# sch_Power.net
KiCad netlist of a schematic drawn in Altium Designer
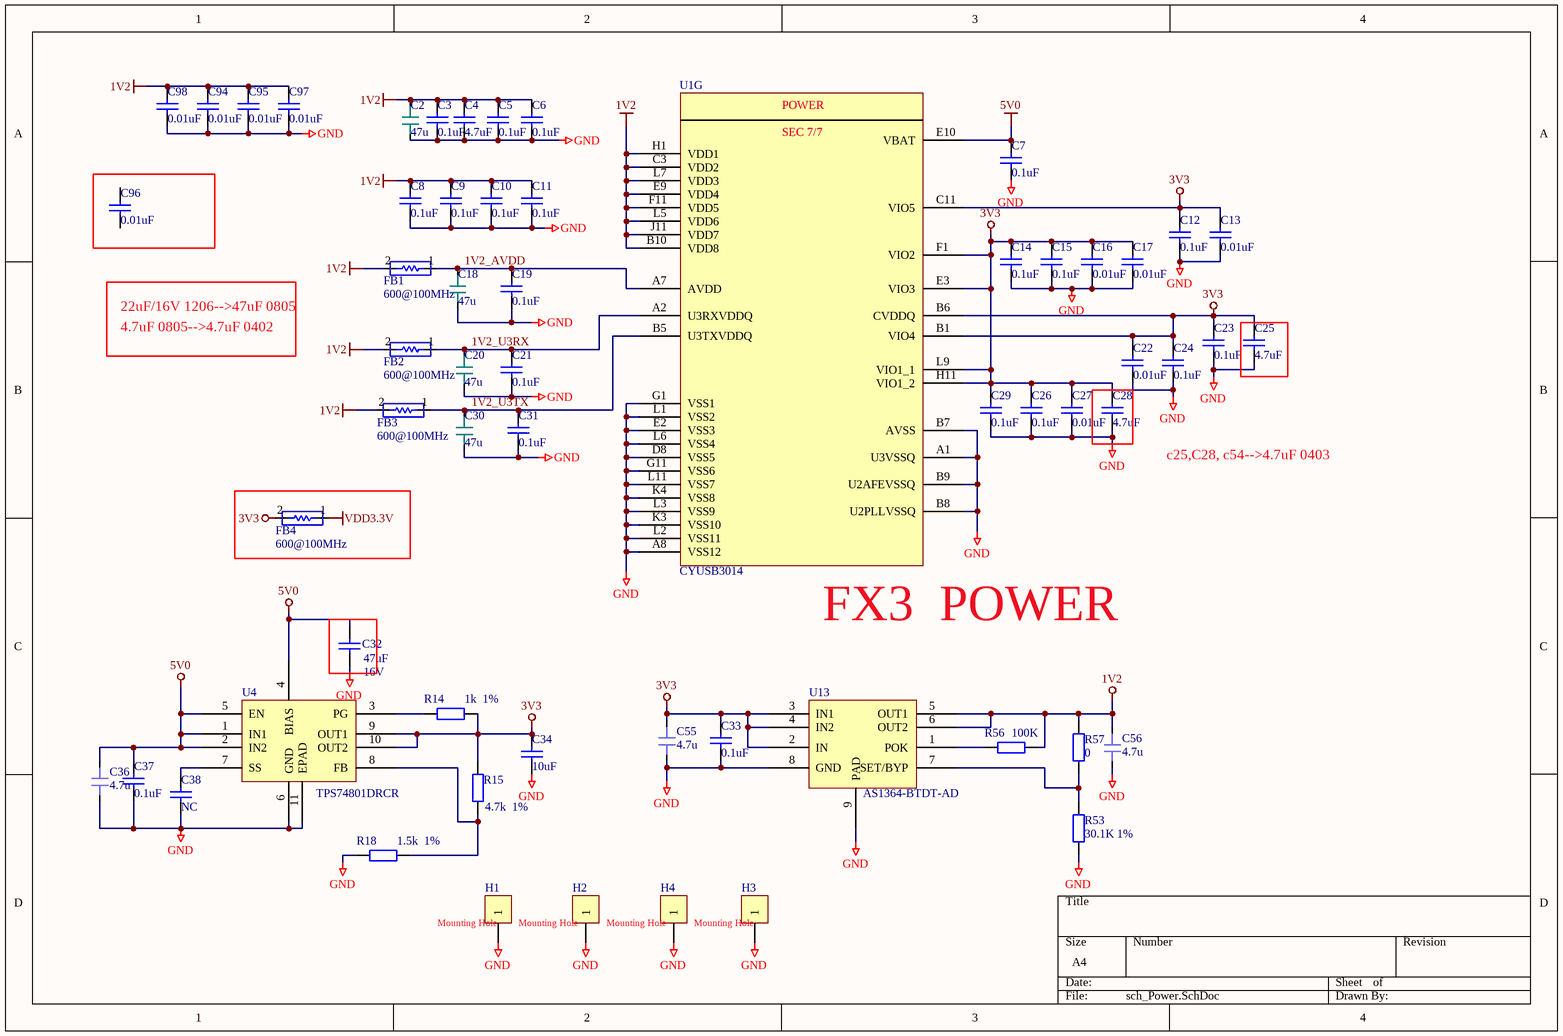
[diagram p0: sch_Power.SchDoc]

(export (version "E")
  (design (tool "Eeschema 10.0.6"))
  (components
    (comp (ref "C2")
      (value "47u")
      (footprint "0805C")
      (description "CC08052B476M5B20D")
      (libsource (lib "V0P1") (part "cap0805"))
    )
    (comp (ref "C3")
      (value "0.1uF")
      (footprint "0402C")
      (description "Capacitor")
      (fields (field (name "PUBLISHER") "Altium Limited"))
      (libsource (lib "Miscellaneous Devices") (part "Cap"))
    )
    (comp (ref "C4")
      (value "4.7uF")
      (footprint "0402C")
      (description "Capacitor")
      (fields (field (name "Comment") "0.1uF") (field (name "PUBLISHER") "Altium Limited"))
      (libsource (lib "Miscellaneous Devices") (part "Cap"))
    )
    (comp (ref "C5")
      (value "0.1uF")
      (footprint "0402C")
      (description "Capacitor")
      (fields (field (name "PUBLISHER") "Altium Limited"))
      (libsource (lib "Miscellaneous Devices") (part "Cap"))
    )
    (comp (ref "C6")
      (value "0.1uF")
      (footprint "0402C")
      (description "Capacitor")
      (fields (field (name "PUBLISHER") "Altium Limited"))
      (libsource (lib "Miscellaneous Devices") (part "Cap"))
    )
    (comp (ref "C7")
      (value "0.1uF")
      (footprint "0402C")
      (description "Capacitor")
      (fields (field (name "PUBLISHER") "Altium Limited"))
      (libsource (lib "Miscellaneous Devices") (part "Cap"))
    )
    (comp (ref "C8")
      (value "0.1uF")
      (footprint "0402C")
      (description "Capacitor")
      (fields (field (name "PUBLISHER") "Altium Limited"))
      (libsource (lib "Miscellaneous Devices") (part "Cap"))
    )
    (comp (ref "C9")
      (value "0.1uF")
      (footprint "0402C")
      (description "Capacitor")
      (fields (field (name "PUBLISHER") "Altium Limited"))
      (libsource (lib "Miscellaneous Devices") (part "Cap"))
    )
    (comp (ref "C10")
      (value "0.1uF")
      (footprint "0402C")
      (description "Capacitor")
      (fields (field (name "PUBLISHER") "Altium Limited"))
      (libsource (lib "Miscellaneous Devices") (part "Cap"))
    )
    (comp (ref "C11")
      (value "0.1uF")
      (footprint "0402C")
      (description "Capacitor")
      (fields (field (name "PUBLISHER") "Altium Limited"))
      (libsource (lib "Miscellaneous Devices") (part "Cap"))
    )
    (comp (ref "C12")
      (value "0.1uF")
      (footprint "0402C")
      (description "Capacitor")
      (fields (field (name "PUBLISHER") "Altium Limited"))
      (libsource (lib "Miscellaneous Devices") (part "Cap"))
    )
    (comp (ref "C13")
      (value "0.01uF")
      (footprint "0402C")
      (description "Capacitor")
      (fields (field (name "PUBLISHER") "Altium Limited"))
      (libsource (lib "Miscellaneous Devices") (part "Cap"))
    )
    (comp (ref "C14")
      (value "0.1uF")
      (footprint "0402C")
      (description "Capacitor")
      (fields (field (name "PUBLISHER") "Altium Limited"))
      (libsource (lib "Miscellaneous Devices") (part "Cap"))
    )
    (comp (ref "C15")
      (value "0.1uF")
      (footprint "0402C")
      (description "Capacitor")
      (fields (field (name "PUBLISHER") "Altium Limited"))
      (libsource (lib "Miscellaneous Devices") (part "Cap"))
    )
    (comp (ref "C16")
      (value "0.01uF")
      (footprint "0402C")
      (description "Capacitor")
      (fields (field (name "PUBLISHER") "Altium Limited"))
      (libsource (lib "Miscellaneous Devices") (part "Cap"))
    )
    (comp (ref "C17")
      (value "0.01uF")
      (footprint "0402C")
      (description "Capacitor")
      (fields (field (name "PUBLISHER") "Altium Limited"))
      (libsource (lib "Miscellaneous Devices") (part "Cap"))
    )
    (comp (ref "C18")
      (value "47u")
      (footprint "0805C")
      (description "CC08052B476M5B20D")
      (libsource (lib "V0P1") (part "cap0805"))
    )
    (comp (ref "C19")
      (value "0.1uF")
      (footprint "0402C")
      (description "Capacitor")
      (fields (field (name "PUBLISHER") "Altium Limited"))
      (libsource (lib "Miscellaneous Devices") (part "Cap"))
    )
    (comp (ref "C20")
      (value "47u")
      (footprint "0805C")
      (description "CC08052B476M5B20D")
      (libsource (lib "V0P1") (part "cap0805"))
    )
    (comp (ref "C21")
      (value "0.1uF")
      (footprint "0402C")
      (description "Capacitor")
      (fields (field (name "PUBLISHER") "Altium Limited"))
      (libsource (lib "Miscellaneous Devices") (part "Cap"))
    )
    (comp (ref "C22")
      (value "0.01uF")
      (footprint "0402C")
      (description "Capacitor")
      (fields (field (name "PUBLISHER") "Altium Limited"))
      (libsource (lib "Miscellaneous Devices") (part "Cap"))
    )
    (comp (ref "C23")
      (value "0.1uF")
      (footprint "0402C")
      (description "Capacitor")
      (fields (field (name "PUBLISHER") "Altium Limited"))
      (libsource (lib "Miscellaneous Devices") (part "Cap"))
    )
    (comp (ref "C24")
      (value "0.1uF")
      (footprint "0402C")
      (description "Capacitor")
      (fields (field (name "PUBLISHER") "Altium Limited"))
      (libsource (lib "Miscellaneous Devices") (part "Cap"))
    )
    (comp (ref "C25")
      (value "4.7uF")
      (footprint "0402C")
      (description "Capacitor")
      (fields (field (name "PUBLISHER") "Altium Limited"))
      (libsource (lib "Miscellaneous Devices") (part "Cap"))
    )
    (comp (ref "C26")
      (value "0.1uF")
      (footprint "0402C")
      (description "Capacitor")
      (fields (field (name "PUBLISHER") "Altium Limited"))
      (libsource (lib "Miscellaneous Devices") (part "Cap"))
    )
    (comp (ref "C27")
      (value "0.01uF")
      (footprint "0402C")
      (description "Capacitor")
      (fields (field (name "PUBLISHER") "Altium Limited"))
      (libsource (lib "Miscellaneous Devices") (part "Cap"))
    )
    (comp (ref "C28")
      (value "4.7uF")
      (footprint "0402C")
      (description "Capacitor")
      (fields (field (name "PUBLISHER") "Altium Limited"))
      (libsource (lib "Miscellaneous Devices") (part "Cap"))
    )
    (comp (ref "C29")
      (value "0.1uF")
      (footprint "0402C")
      (description "Capacitor")
      (fields (field (name "PUBLISHER") "Altium Limited"))
      (libsource (lib "Miscellaneous Devices") (part "Cap"))
    )
    (comp (ref "C30")
      (value "47u")
      (footprint "0805C")
      (description "CC08052B476M5B20D")
      (libsource (lib "V0P1") (part "cap0805"))
    )
    (comp (ref "C31")
      (value "0.1uF")
      (footprint "0402C")
      (description "Capacitor")
      (fields (field (name "PUBLISHER") "Altium Limited"))
      (libsource (lib "Miscellaneous Devices") (part "Cap"))
    )
    (comp (ref "C32")
      (value "47uF")
      (footprint "0805C")
      (description "Capacitor")
      (fields (field (name "ALTIUM_VALUE") "16V") (field (name "PUBLISHER") "Altium Limited"))
      (libsource (lib "Miscellaneous Devices") (part "Cap"))
    )
    (comp (ref "C33")
      (value "0.1uF")
      (footprint "0402C")
      (description "Capacitor")
      (fields (field (name "PUBLISHER") "Altium Limited"))
      (libsource (lib "Miscellaneous Devices") (part "Cap"))
    )
    (comp (ref "C34")
      (value "10uF")
      (footprint "0805C")
      (description "Capacitor")
      (fields (field (name "PUBLISHER") "Altium Limited"))
      (libsource (lib "Miscellaneous Devices") (part "Cap"))
    )
    (comp (ref "C36")
      (value "4.7u")
      (footprint "0402C")
      (description "CC0402MRX5R5BB475")
      (libsource (lib "V0P1") (part "cap0402"))
    )
    (comp (ref "C37")
      (value "0.1uF")
      (footprint "0402C")
      (description "Capacitor")
      (fields (field (name "PUBLISHER") "Altium Limited"))
      (libsource (lib "Miscellaneous Devices") (part "Cap"))
    )
    (comp (ref "C38")
      (value "NC")
      (footprint "0402C")
      (description "Capacitor")
      (fields (field (name "PUBLISHER") "Altium Limited"))
      (libsource (lib "Miscellaneous Devices") (part "Cap"))
    )
    (comp (ref "C55")
      (value "4.7u")
      (footprint "0402C")
      (description "CC0402MRX5R5BB475")
      (libsource (lib "V0P1") (part "cap0402"))
    )
    (comp (ref "C56")
      (value "4.7u")
      (footprint "0402C")
      (description "CC0402MRX5R5BB475")
      (libsource (lib "V0P1") (part "cap0402"))
    )
    (comp (ref "C94")
      (value "0.01uF")
      (footprint "0402C")
      (description "Capacitor")
      (fields (field (name "PUBLISHER") "Altium Limited"))
      (libsource (lib "Miscellaneous Devices") (part "Cap"))
    )
    (comp (ref "C95")
      (value "0.01uF")
      (footprint "0402C")
      (description "Capacitor")
      (fields (field (name "PUBLISHER") "Altium Limited"))
      (libsource (lib "Miscellaneous Devices") (part "Cap"))
    )
    (comp (ref "C96")
      (value "0.01uF")
      (footprint "0402C")
      (description "Capacitor")
      (fields (field (name "PUBLISHER") "Altium Limited"))
      (libsource (lib "Miscellaneous Devices") (part "Cap"))
    )
    (comp (ref "C97")
      (value "0.01uF")
      (footprint "0402C")
      (description "Capacitor")
      (fields (field (name "PUBLISHER") "Altium Limited"))
      (libsource (lib "Miscellaneous Devices") (part "Cap"))
    )
    (comp (ref "C98")
      (value "0.01uF")
      (footprint "0402C")
      (description "Capacitor")
      (fields (field (name "PUBLISHER") "Altium Limited"))
      (libsource (lib "Miscellaneous Devices") (part "Cap"))
    )
    (comp (ref "FB1") (value "600@100MHz") (footprint "0603R") (libsource (lib "TXW") (part "600@100MHz")))
    (comp (ref "FB2") (value "600@100MHz") (footprint "0603R") (libsource (lib "TXW") (part "600@100MHz")))
    (comp (ref "FB3") (value "600@100MHz") (footprint "0603R") (libsource (lib "TXW") (part "600@100MHz")))
    (comp (ref "FB4") (value "600@100MHz") (footprint "0603R") (libsource (lib "TXW") (part "600@100MHz")))
    (comp (ref "H1")
      (value "CON1")
      (footprint "PAD_M3_D350_450")
      (description "Connector")
      (libsource (lib "SuperSchLib") (part "CON1"))
    )
    (comp (ref "H2")
      (value "CON1")
      (footprint "PAD_M3_D350_450")
      (description "Connector")
      (libsource (lib "SuperSchLib") (part "CON1"))
    )
    (comp (ref "H3")
      (value "CON1")
      (footprint "PAD_M3_D350_450")
      (description "Connector")
      (libsource (lib "SuperSchLib") (part "CON1"))
    )
    (comp (ref "H4")
      (value "CON1")
      (footprint "PAD_M3_D350_450")
      (description "Connector")
      (libsource (lib "SuperSchLib") (part "CON1"))
    )
    (comp (ref "R14")
      (value "1k  1%")
      (footprint "0402R")
      (description "Resistor")
      (fields (field (name "Comment") "1K") (field (name "PUBLISHER") "Altium Limited"))
      (libsource (lib "") (part "Resistor_1"))
    )
    (comp (ref "R15")
      (value "4.7k  1%")
      (footprint "0402R")
      (description "Resistor")
      (fields (field (name "Comment") "4.7K") (field (name "PUBLISHER") "Altium Limited"))
      (libsource (lib "SZG") (part "Resistor"))
    )
    (comp (ref "R18")
      (value "1.5k  1%")
      (footprint "0402R")
      (description "Resistor")
      (fields (field (name "Comment") "1.5K") (field (name "PUBLISHER") "Altium Limited"))
      (libsource (lib "") (part "Resistor_1"))
    )
    (comp (ref "R53")
      (value "30.1K 1%")
      (footprint "0402R")
      (description "Resistor")
      (fields (field (name "Comment") "30.1K") (field (name "PUBLISHER") "Altium Limited"))
      (libsource (lib "SZG") (part "Resistor"))
    )
    (comp (ref "R56")
      (value "100K")
      (footprint "0402R")
      (description "Resistor")
      (fields (field (name "PUBLISHER") "Altium Limited"))
      (libsource (lib "") (part "Resistor_1"))
    )
    (comp (ref "R57")
      (value "0")
      (footprint "0402R")
      (description "Resistor")
      (fields (field (name "Comment") "0R") (field (name "PUBLISHER") "Altium Limited"))
      (libsource (lib "SZG") (part "Resistor"))
    )
    (comp (ref "U1")
      (value "CYUSB3014")
      (footprint "FBGA121_P80L100W100H11")
      (libsource (lib "TXW") (part "CYUSB3014"))
    )
    (comp (ref "U4")
      (value "TPS74801DRCR")
      (footprint "SON10_P50L32W32H10_DRC")
      (libsource (lib "TXW") (part "TPS74801DRCR"))
    )
    (comp (ref "U13")
      (value "AS1364-BTDT-AD")
      (footprint "TDFN8_P65L30W30H08")
      (libsource (lib "TXW") (part "AS1364-BTDT-AD"))
    )
  )
  (nets
    (net (code "1") (name "/1V2_AVDD") (class "Default")
      (node (ref "C18") (pin "1") (pinfunction "1_1") (pintype "passive"))
      (node (ref "C19") (pin "2") (pinfunction "2_2") (pintype "passive"))
      (node (ref "FB1") (pin "1") (pinfunction "1_1") (pintype "passive"))
      (node (ref "U1") (pin "A7") (pinfunction "AVDD_A7") (pintype "passive"))
    )
    (net (code "2") (name "/1V2_U3RX") (class "Default")
      (node (ref "C20") (pin "1") (pinfunction "1_1") (pintype "passive"))
      (node (ref "C21") (pin "2") (pinfunction "2_2") (pintype "passive"))
      (node (ref "FB2") (pin "1") (pinfunction "1_1") (pintype "passive"))
      (node (ref "U1") (pin "A2") (pinfunction "U3RXVDDQ_A2") (pintype "passive"))
    )
    (net (code "3") (name "/1V2_U3TX") (class "Default")
      (node (ref "C30") (pin "1") (pinfunction "1_1") (pintype "passive"))
      (node (ref "C31") (pin "2") (pinfunction "2_2") (pintype "passive"))
      (node (ref "FB3") (pin "1") (pinfunction "1_1") (pintype "passive"))
      (node (ref "U1") (pin "B5") (pinfunction "U3TXVDDQ_B5") (pintype "passive"))
    )
    (net (code "4") (name "1V2") (class "Default")
      (node (ref "C10") (pin "2") (pinfunction "2_2") (pintype "passive"))
      (node (ref "C11") (pin "2") (pinfunction "2_2") (pintype "passive"))
      (node (ref "C2") (pin "1") (pinfunction "1_1") (pintype "passive"))
      (node (ref "C3") (pin "2") (pinfunction "2_2") (pintype "passive"))
      (node (ref "C4") (pin "2") (pinfunction "2_2") (pintype "passive"))
      (node (ref "C5") (pin "2") (pinfunction "2_2") (pintype "passive"))
      (node (ref "C56") (pin "1") (pinfunction "1_1") (pintype "passive"))
      (node (ref "C6") (pin "2") (pinfunction "2_2") (pintype "passive"))
      (node (ref "C8") (pin "2") (pinfunction "2_2") (pintype "passive"))
      (node (ref "C9") (pin "2") (pinfunction "2_2") (pintype "passive"))
      (node (ref "C94") (pin "2") (pinfunction "2_2") (pintype "passive"))
      (node (ref "C95") (pin "2") (pinfunction "2_2") (pintype "passive"))
      (node (ref "C97") (pin "2") (pinfunction "2_2") (pintype "passive"))
      (node (ref "C98") (pin "2") (pinfunction "2_2") (pintype "passive"))
      (node (ref "FB1") (pin "2") (pinfunction "2_2") (pintype "passive"))
      (node (ref "FB2") (pin "2") (pinfunction "2_2") (pintype "passive"))
      (node (ref "FB3") (pin "2") (pinfunction "2_2") (pintype "passive"))
      (node (ref "R56") (pin "1") (pinfunction "1_1") (pintype "passive"))
      (node (ref "R57") (pin "1") (pinfunction "1_1") (pintype "passive"))
      (node (ref "U1") (pin "B10") (pinfunction "VDD8_B10") (pintype "passive"))
      (node (ref "U1") (pin "C3") (pinfunction "VDD2_C3") (pintype "passive"))
      (node (ref "U1") (pin "E9") (pinfunction "VDD4_E9") (pintype "passive"))
      (node (ref "U1") (pin "F11") (pinfunction "VDD5_F11") (pintype "passive"))
      (node (ref "U1") (pin "H1") (pinfunction "VDD1_H1") (pintype "passive"))
      (node (ref "U1") (pin "J11") (pinfunction "VDD7_J11") (pintype "passive"))
      (node (ref "U1") (pin "L5") (pinfunction "VDD6_L5") (pintype "passive"))
      (node (ref "U1") (pin "L7") (pinfunction "VDD3_L7") (pintype "passive"))
      (node (ref "U13") (pin "5") (pinfunction "OUT1_5") (pintype "passive"))
      (node (ref "U13") (pin "6") (pinfunction "OUT2_6") (pintype "passive"))
    )
    (net (code "5") (name "3V3") (class "Default")
      (node (ref "C12") (pin "2") (pinfunction "2_2") (pintype "passive"))
      (node (ref "C13") (pin "2") (pinfunction "2_2") (pintype "passive"))
      (node (ref "C14") (pin "2") (pinfunction "2_2") (pintype "passive"))
      (node (ref "C15") (pin "2") (pinfunction "2_2") (pintype "passive"))
      (node (ref "C16") (pin "2") (pinfunction "2_2") (pintype "passive"))
      (node (ref "C17") (pin "2") (pinfunction "2_2") (pintype "passive"))
      (node (ref "C22") (pin "2") (pinfunction "2_2") (pintype "passive"))
      (node (ref "C23") (pin "2") (pinfunction "2_2") (pintype "passive"))
      (node (ref "C24") (pin "2") (pinfunction "2_2") (pintype "passive"))
      (node (ref "C25") (pin "2") (pinfunction "2_2") (pintype "passive"))
      (node (ref "C26") (pin "2") (pinfunction "2_2") (pintype "passive"))
      (node (ref "C27") (pin "2") (pinfunction "2_2") (pintype "passive"))
      (node (ref "C28") (pin "2") (pinfunction "2_2") (pintype "passive"))
      (node (ref "C29") (pin "2") (pinfunction "2_2") (pintype "passive"))
      (node (ref "C33") (pin "2") (pinfunction "2_2") (pintype "passive"))
      (node (ref "C34") (pin "2") (pinfunction "2_2") (pintype "passive"))
      (node (ref "C55") (pin "1") (pinfunction "1_1") (pintype "passive"))
      (node (ref "FB4") (pin "2") (pinfunction "2_2") (pintype "passive"))
      (node (ref "R14") (pin "1") (pinfunction "1_1") (pintype "passive"))
      (node (ref "R15") (pin "1") (pinfunction "1_1") (pintype "passive"))
      (node (ref "U1") (pin "B1") (pinfunction "VIO4_B1") (pintype "passive"))
      (node (ref "U1") (pin "B6") (pinfunction "CVDDQ_B6") (pintype "passive"))
      (node (ref "U1") (pin "C11") (pinfunction "VIO5_C11") (pintype "power_in"))
      (node (ref "U1") (pin "E3") (pinfunction "VIO3_E3") (pintype "passive"))
      (node (ref "U1") (pin "F1") (pinfunction "VIO2_F1") (pintype "passive"))
      (node (ref "U1") (pin "H11") (pinfunction "VIO1_2_H11") (pintype "passive"))
      (node (ref "U1") (pin "L9") (pinfunction "VIO1_1_L9") (pintype "passive"))
      (node (ref "U13") (pin "2") (pinfunction "IN_2") (pintype "passive"))
      (node (ref "U13") (pin "3") (pinfunction "IN1_3") (pintype "passive"))
      (node (ref "U13") (pin "4") (pinfunction "IN2_4") (pintype "passive"))
      (node (ref "U4") (pin "10") (pinfunction "OUT2_10") (pintype "passive"))
      (node (ref "U4") (pin "9") (pinfunction "OUT1_9") (pintype "passive"))
    )
    (net (code "6") (name "5V0") (class "Default")
      (node (ref "C32") (pin "1") (pinfunction "1_1") (pintype "passive"))
      (node (ref "C36") (pin "1") (pinfunction "1_1") (pintype "passive"))
      (node (ref "C37") (pin "2") (pinfunction "2_2") (pintype "passive"))
      (node (ref "C7") (pin "2") (pinfunction "2_2") (pintype "passive"))
      (node (ref "U1") (pin "E10") (pinfunction "VBAT_E10") (pintype "passive"))
      (node (ref "U4") (pin "1") (pinfunction "IN1_1") (pintype "passive"))
      (node (ref "U4") (pin "2") (pinfunction "IN2_2") (pintype "passive"))
      (node (ref "U4") (pin "4") (pinfunction "BIAS_4") (pintype "passive"))
      (node (ref "U4") (pin "5") (pinfunction "EN_5") (pintype "passive"))
    )
    (net (code "7") (name "GND") (class "Default")
      (node (ref "C10") (pin "1") (pinfunction "1_1") (pintype "passive"))
      (node (ref "C11") (pin "1") (pinfunction "1_1") (pintype "passive"))
      (node (ref "C12") (pin "1") (pinfunction "1_1") (pintype "passive"))
      (node (ref "C13") (pin "1") (pinfunction "1_1") (pintype "passive"))
      (node (ref "C14") (pin "1") (pinfunction "1_1") (pintype "passive"))
      (node (ref "C15") (pin "1") (pinfunction "1_1") (pintype "passive"))
      (node (ref "C16") (pin "1") (pinfunction "1_1") (pintype "passive"))
      (node (ref "C17") (pin "1") (pinfunction "1_1") (pintype "passive"))
      (node (ref "C18") (pin "2") (pinfunction "2_2") (pintype "passive"))
      (node (ref "C19") (pin "1") (pinfunction "1_1") (pintype "passive"))
      (node (ref "C2") (pin "2") (pinfunction "2_2") (pintype "passive"))
      (node (ref "C20") (pin "2") (pinfunction "2_2") (pintype "passive"))
      (node (ref "C21") (pin "1") (pinfunction "1_1") (pintype "passive"))
      (node (ref "C22") (pin "1") (pinfunction "1_1") (pintype "passive"))
      (node (ref "C23") (pin "1") (pinfunction "1_1") (pintype "passive"))
      (node (ref "C24") (pin "1") (pinfunction "1_1") (pintype "passive"))
      (node (ref "C25") (pin "1") (pinfunction "1_1") (pintype "passive"))
      (node (ref "C26") (pin "1") (pinfunction "1_1") (pintype "passive"))
      (node (ref "C27") (pin "1") (pinfunction "1_1") (pintype "passive"))
      (node (ref "C28") (pin "1") (pinfunction "1_1") (pintype "passive"))
      (node (ref "C29") (pin "1") (pinfunction "1_1") (pintype "passive"))
      (node (ref "C3") (pin "1") (pinfunction "1_1") (pintype "passive"))
      (node (ref "C30") (pin "2") (pinfunction "2_2") (pintype "passive"))
      (node (ref "C31") (pin "1") (pinfunction "1_1") (pintype "passive"))
      (node (ref "C32") (pin "2") (pinfunction "2_2") (pintype "passive"))
      (node (ref "C33") (pin "1") (pinfunction "1_1") (pintype "passive"))
      (node (ref "C34") (pin "1") (pinfunction "1_1") (pintype "passive"))
      (node (ref "C36") (pin "2") (pinfunction "2_2") (pintype "passive"))
      (node (ref "C37") (pin "1") (pinfunction "1_1") (pintype "passive"))
      (node (ref "C38") (pin "1") (pinfunction "1_1") (pintype "passive"))
      (node (ref "C4") (pin "1") (pinfunction "1_1") (pintype "passive"))
      (node (ref "C5") (pin "1") (pinfunction "1_1") (pintype "passive"))
      (node (ref "C55") (pin "2") (pinfunction "2_2") (pintype "passive"))
      (node (ref "C56") (pin "2") (pinfunction "2_2") (pintype "passive"))
      (node (ref "C6") (pin "1") (pinfunction "1_1") (pintype "passive"))
      (node (ref "C7") (pin "1") (pinfunction "1_1") (pintype "passive"))
      (node (ref "C8") (pin "1") (pinfunction "1_1") (pintype "passive"))
      (node (ref "C9") (pin "1") (pinfunction "1_1") (pintype "passive"))
      (node (ref "C94") (pin "1") (pinfunction "1_1") (pintype "passive"))
      (node (ref "C95") (pin "1") (pinfunction "1_1") (pintype "passive"))
      (node (ref "C97") (pin "1") (pinfunction "1_1") (pintype "passive"))
      (node (ref "C98") (pin "1") (pinfunction "1_1") (pintype "passive"))
      (node (ref "H1") (pin "1") (pinfunction "1_1") (pintype "passive"))
      (node (ref "H2") (pin "1") (pinfunction "1_1") (pintype "passive"))
      (node (ref "H3") (pin "1") (pinfunction "1_1") (pintype "passive"))
      (node (ref "H4") (pin "1") (pinfunction "1_1") (pintype "passive"))
      (node (ref "R18") (pin "2") (pinfunction "2_2") (pintype "passive"))
      (node (ref "R53") (pin "2") (pinfunction "2_2") (pintype "passive"))
      (node (ref "U1") (pin "A1") (pinfunction "U3VSSQ_A1") (pintype "passive"))
      (node (ref "U1") (pin "A8") (pinfunction "VSS12_A8") (pintype "passive"))
      (node (ref "U1") (pin "B7") (pinfunction "AVSS_B7") (pintype "passive"))
      (node (ref "U1") (pin "B8") (pinfunction "U2PLLVSSQ_B8") (pintype "passive"))
      (node (ref "U1") (pin "B9") (pinfunction "U2AFEVSSQ_B9") (pintype "passive"))
      (node (ref "U1") (pin "D8") (pinfunction "VSS5_D8") (pintype "passive"))
      (node (ref "U1") (pin "E2") (pinfunction "VSS3_E2") (pintype "passive"))
      (node (ref "U1") (pin "G1") (pinfunction "VSS1_G1") (pintype "passive"))
      (node (ref "U1") (pin "G11") (pinfunction "VSS6_G11") (pintype "passive"))
      (node (ref "U1") (pin "K3") (pinfunction "VSS10_K3") (pintype "passive"))
      (node (ref "U1") (pin "K4") (pinfunction "VSS8_K4") (pintype "passive"))
      (node (ref "U1") (pin "L1") (pinfunction "VSS2_L1") (pintype "passive"))
      (node (ref "U1") (pin "L11") (pinfunction "VSS7_L11") (pintype "passive"))
      (node (ref "U1") (pin "L2") (pinfunction "VSS11_L2") (pintype "passive"))
      (node (ref "U1") (pin "L3") (pinfunction "VSS9_L3") (pintype "passive"))
      (node (ref "U1") (pin "L6") (pinfunction "VSS4_L6") (pintype "passive"))
      (node (ref "U13") (pin "8") (pinfunction "GND_8") (pintype "passive"))
      (node (ref "U13") (pin "9") (pinfunction "PAD_9") (pintype "passive"))
      (node (ref "U4") (pin "11") (pinfunction "EPAD_11") (pintype "passive"))
      (node (ref "U4") (pin "6") (pinfunction "GND_6") (pintype "passive"))
    )
    (net (code "8") (name "Net-(U4-FB)") (class "Default")
      (node (ref "R15") (pin "2") (pinfunction "2_2") (pintype "passive"))
      (node (ref "R18") (pin "1") (pinfunction "1_1") (pintype "passive"))
      (node (ref "U4") (pin "8") (pinfunction "FB_8") (pintype "passive"))
    )
    (net (code "9") (name "Net-(U4-PG)") (class "Default")
      (node (ref "R14") (pin "2") (pinfunction "2_2") (pintype "passive"))
      (node (ref "U4") (pin "3") (pinfunction "PG_3") (pintype "passive"))
    )
    (net (code "10") (name "Net-(U4-SS)") (class "Default")
      (node (ref "C38") (pin "2") (pinfunction "2_2") (pintype "passive"))
      (node (ref "U4") (pin "7") (pinfunction "SS_7") (pintype "passive"))
    )
    (net (code "11") (name "Net-(U13-POK)") (class "Default")
      (node (ref "R56") (pin "2") (pinfunction "2_2") (pintype "passive"))
      (node (ref "U13") (pin "1") (pinfunction "POK_1") (pintype "passive"))
    )
    (net (code "12") (name "Net-(U13-SET{slash}BYP)") (class "Default")
      (node (ref "R53") (pin "1") (pinfunction "1_1") (pintype "passive"))
      (node (ref "R57") (pin "2") (pinfunction "2_2") (pintype "passive"))
      (node (ref "U13") (pin "7") (pinfunction "SET/BYP_7") (pintype "passive"))
    )
    (net (code "13") (name "VDD3.3V") (class "Default")
      (node (ref "FB4") (pin "1") (pinfunction "1_1") (pintype "passive"))
    )
    (net (code "14") (name "unconnected-(C96-Pad1)") (class "Default")
      (node (ref "C96") (pin "1") (pinfunction "1_1") (pintype "passive"))
    )
    (net (code "15") (name "unconnected-(C96-Pad2)") (class "Default")
      (node (ref "C96") (pin "2") (pinfunction "2_2") (pintype "passive"))
    )
  )
)
